# ospi_v11.net
KiCad netlist of a schematic drawn in EAGLE
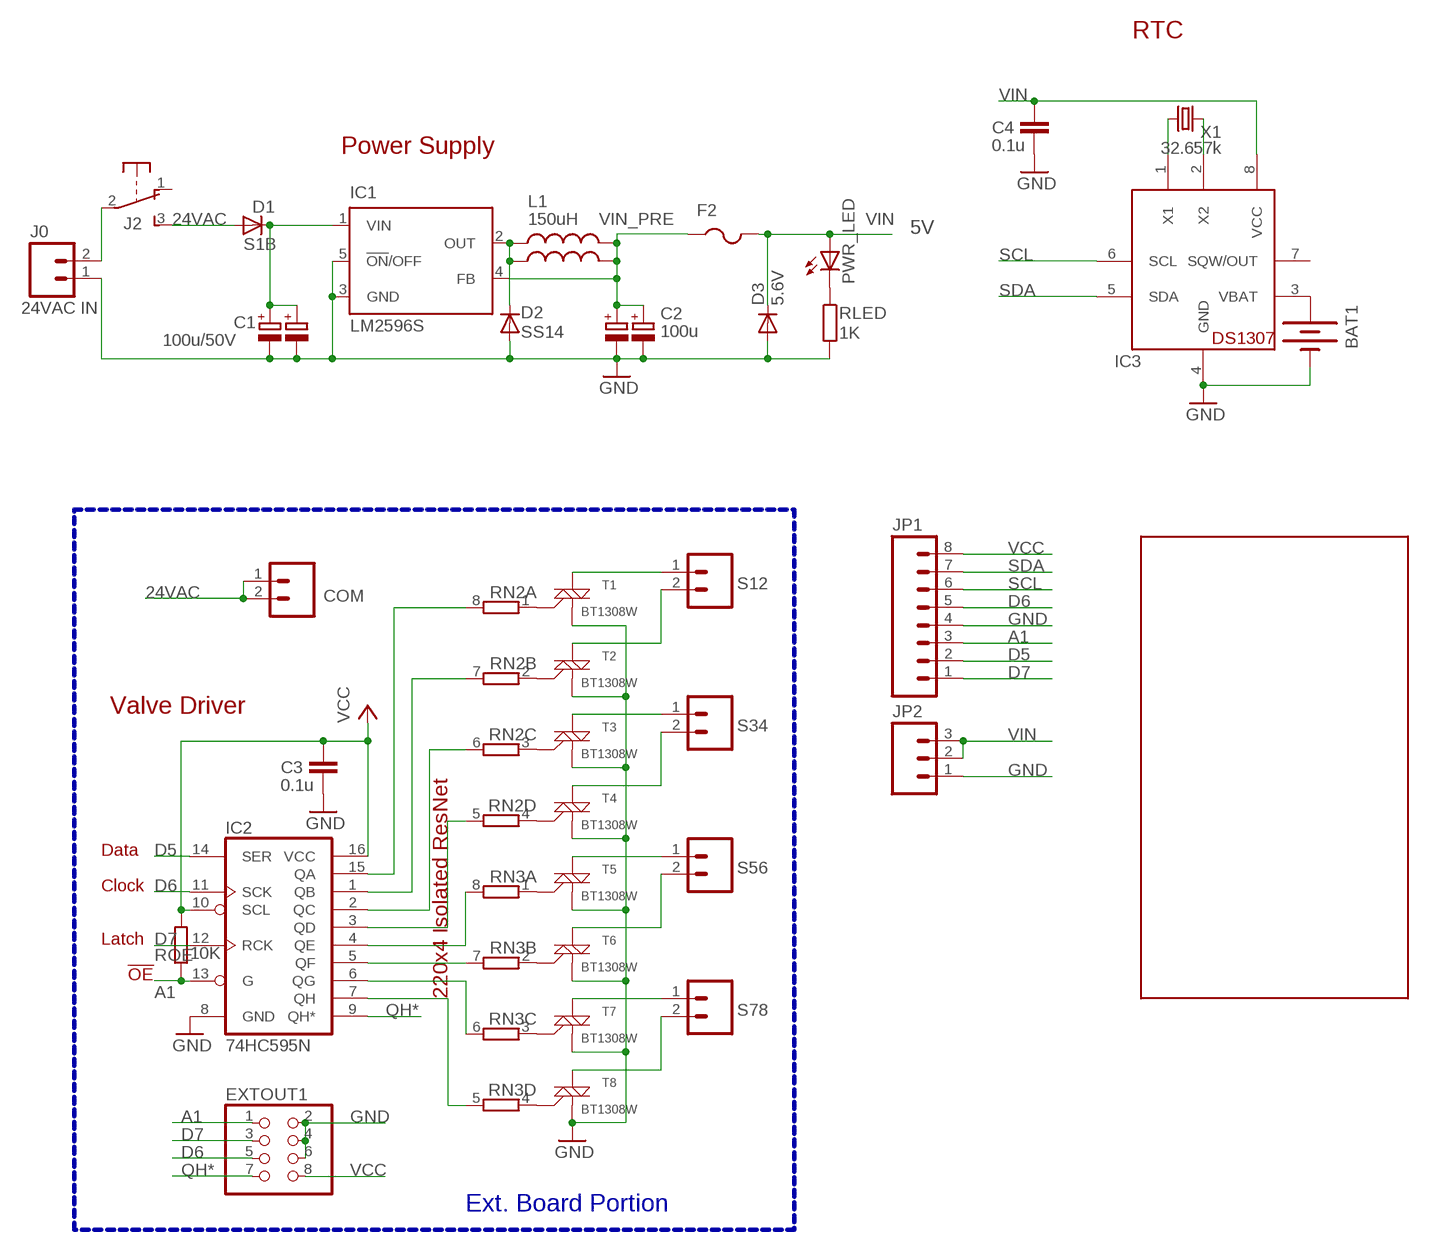
[diagram p0: schematic, sheet 1]

(export (version "E")
  (design (tool "Eeschema 10.0.6"))
  (components
    (comp (ref "BAT1")
      (value "BATTERYBATTERY_12MM_SMT")
      (footprint "eagle-import:BATTCON_12MM_SMT")
      (libsource (lib "eagle-import") (part "BATTERYBATTERY_12MM_SMT"))
    )
    (comp (ref "C1")
      (value "100u/50V")
      (footprint "eagle-import:E3,5-8")
      (libsource (lib "eagle-import") (part "CPOL-EUE3.5-8"))
    )
    (comp (ref "C1'")
      (value "100u")
      (footprint "eagle-import:PANASONIC_E")
      (libsource (lib "eagle-import") (part "CPOL-EUE"))
    )
    (comp (ref "C2")
      (value "100u")
      (footprint "eagle-import:E3,5-8")
      (libsource (lib "eagle-import") (part "CPOL-EUE3.5-8"))
    )
    (comp (ref "C2'")
      (value "100u")
      (footprint "eagle-import:PANASONIC_E")
      (libsource (lib "eagle-import") (part "CPOL-EUE"))
    )
    (comp (ref "C3")
      (value "0.1u")
      (footprint "eagle-import:C0805")
      (libsource (lib "eagle-import") (part "C-EUC0805"))
    )
    (comp (ref "C4")
      (value "0.1u")
      (footprint "eagle-import:C0805")
      (libsource (lib "eagle-import") (part "C-EUC0805"))
    )
    (comp (ref "COM")
      (value "M025MM")
      (footprint "eagle-import:SCREWTERMINAL-5MM-2")
      (libsource (lib "eagle-import") (part "M025MM"))
    )
    (comp (ref "D1")
      (value "S1B")
      (footprint "eagle-import:DO-214AC")
      (libsource (lib "eagle-import") (part "DIODE-DO-214AC"))
    )
    (comp (ref "D2")
      (value "SS14")
      (footprint "eagle-import:DO-214AC")
      (libsource (lib "eagle-import") (part "DIODE-DO-214AC"))
    )
    (comp (ref "D3")
      (value "5.6V")
      (footprint "eagle-import:MINIMELF")
      (libsource (lib "eagle-import") (part "DIODE-MINIMELF"))
    )
    (comp (ref "EXTOUT1")
      (value "PINHD-2X4/90")
      (footprint "eagle-import:2X04_90")
      (libsource (lib "eagle-import") (part "PINHD-2X4/90"))
    )
    (comp (ref "F2")
      (value "PTCFUSE-1812")
      (footprint "eagle-import:1812")
      (libsource (lib "eagle-import") (part "PTCFUSE-1812"))
    )
    (comp (ref "IC1")
      (value "LM2596S")
      (footprint "eagle-import:TO263-5")
      (fields (field (name "MF") "NATIONAL SEMICONDUCTOR") (field (name "MPN") "LM2596S-ADJ/NOPB"))
      (libsource (lib "eagle-import") (part "LM2596S"))
    )
    (comp (ref "IC2")
      (value "74HC595N")
      (footprint "eagle-import:SO16")
      (libsource (lib "eagle-import") (part "74595DLS"))
    )
    (comp (ref "IC3")
      (value "DS1307")
      (footprint "eagle-import:SO08")
      (libsource (lib "eagle-import") (part "DS1307SOIC"))
    )
    (comp (ref "J0")
      (value "24VAC IN")
      (footprint "eagle-import:SCREWTERMINAL-5MM-2")
      (libsource (lib "eagle-import") (part "M025MM"))
    )
    (comp (ref "J2")
      (value "EG1206")
      (footprint "eagle-import:EG1206")
      (libsource (lib "eagle-import") (part "EG1206"))
    )
    (comp (ref "JP1")
      (value "M08LOCK")
      (footprint "eagle-import:1X08_LOCK")
      (libsource (lib "eagle-import") (part "M08LOCK"))
    )
    (comp (ref "JP2")
      (value "M03LOCK")
      (footprint "eagle-import:1X03_LOCK")
      (libsource (lib "eagle-import") (part "M03LOCK"))
    )
    (comp (ref "L1")
      (value "150uH")
      (footprint "eagle-import:CDRH125")
      (libsource (lib "eagle-import") (part "INDUCTORPWR"))
    )
    (comp (ref "L1'")
      (value "100uH")
      (footprint "eagle-import:6000-XXXX-RC")
      (libsource (lib "eagle-import") (part "L-US6000-XXX-RC"))
    )
    (comp (ref "PWR_LED")
      (value "LEDCHIPLED_0805")
      (footprint "eagle-import:CHIPLED_0805")
      (libsource (lib "eagle-import") (part "LEDCHIPLED_0805"))
    )
    (comp (ref "RLED")
      (value "1K")
      (footprint "eagle-import:R0805")
      (libsource (lib "eagle-import") (part "R-EU_R0805"))
    )
    (comp (ref "RN2")
      (value "4R-NEXB38V")
      (footprint "eagle-import:EXB38V")
      (libsource (lib "eagle-import") (part "4R-NEXB38V"))
    )
    (comp (ref "RN3")
      (value "4R-NEXB38V")
      (footprint "eagle-import:EXB38V")
      (libsource (lib "eagle-import") (part "4R-NEXB38V"))
    )
    (comp (ref "ROE")
      (value "10K")
      (footprint "eagle-import:R0805")
      (libsource (lib "eagle-import") (part "R-EU_R0805"))
    )
    (comp (ref "S12")
      (value "M025MM")
      (footprint "eagle-import:SCREWTERMINAL-5MM-2")
      (libsource (lib "eagle-import") (part "M025MM"))
    )
    (comp (ref "S34")
      (value "M025MM")
      (footprint "eagle-import:SCREWTERMINAL-5MM-2")
      (libsource (lib "eagle-import") (part "M025MM"))
    )
    (comp (ref "S56")
      (value "M025MM")
      (footprint "eagle-import:SCREWTERMINAL-5MM-2")
      (libsource (lib "eagle-import") (part "M025MM"))
    )
    (comp (ref "S78")
      (value "M025MM")
      (footprint "eagle-import:SCREWTERMINAL-5MM-2")
      (libsource (lib "eagle-import") (part "M025MM"))
    )
    (comp (ref "T1")
      (value "BT1308W")
      (footprint "eagle-import:SOT223")
      (libsource (lib "eagle-import") (part "MAC97SOT223"))
    )
    (comp (ref "T2")
      (value "BT1308W")
      (footprint "eagle-import:SOT223")
      (libsource (lib "eagle-import") (part "MAC97SOT223"))
    )
    (comp (ref "T3")
      (value "BT1308W")
      (footprint "eagle-import:SOT223")
      (libsource (lib "eagle-import") (part "MAC97SOT223"))
    )
    (comp (ref "T4")
      (value "BT1308W")
      (footprint "eagle-import:SOT223")
      (libsource (lib "eagle-import") (part "MAC97SOT223"))
    )
    (comp (ref "T5")
      (value "BT1308W")
      (footprint "eagle-import:SOT223")
      (libsource (lib "eagle-import") (part "MAC97SOT223"))
    )
    (comp (ref "T6")
      (value "BT1308W")
      (footprint "eagle-import:SOT223")
      (libsource (lib "eagle-import") (part "MAC97SOT223"))
    )
    (comp (ref "T7")
      (value "BT1308W")
      (footprint "eagle-import:SOT223")
      (libsource (lib "eagle-import") (part "MAC97SOT223"))
    )
    (comp (ref "T8")
      (value "BT1308W")
      (footprint "eagle-import:SOT223")
      (libsource (lib "eagle-import") (part "MAC97SOT223"))
    )
    (comp (ref "U$2")
      (value "OSPI")
      (footprint "eagle-import:OSPI")
      (libsource (lib "eagle-import") (part "OSPI"))
    )
    (comp (ref "X1")
      (value "32.657k")
      (footprint "eagle-import:MM20SS")
      (libsource (lib "eagle-import") (part "CRYSTALMM20SS"))
    )
  )
  (nets
    (net (code "1") (name "/24VAC") (class "Default")
      (node (ref "COM") (pin "1") (pinfunction "1_1") (pintype "passive"))
      (node (ref "COM") (pin "2") (pinfunction "2_2") (pintype "passive"))
      (node (ref "D1") (pin "A") (pinfunction "A_A") (pintype "passive"))
      (node (ref "J2") (pin "3") (pinfunction "S_3") (pintype "passive"))
    )
    (net (code "2") (name "/A1") (class "Default")
      (node (ref "EXTOUT1") (pin "1") (pinfunction "1_1") (pintype "passive"))
      (node (ref "IC2") (pin "13") (pinfunction "G_13") (pintype "input"))
      (node (ref "JP1") (pin "3") (pinfunction "3_3") (pintype "passive"))
      (node (ref "ROE") (pin "1") (pinfunction "1_1") (pintype "passive"))
    )
    (net (code "3") (name "/D5") (class "Default")
      (node (ref "IC2") (pin "14") (pinfunction "SER_14") (pintype "input"))
      (node (ref "JP1") (pin "2") (pinfunction "2_2") (pintype "passive"))
    )
    (net (code "4") (name "/D6") (class "Default")
      (node (ref "EXTOUT1") (pin "5") (pinfunction "5_5") (pintype "passive"))
      (node (ref "IC2") (pin "11") (pinfunction "SCK_11") (pintype "input"))
      (node (ref "JP1") (pin "5") (pinfunction "5_5") (pintype "passive"))
    )
    (net (code "5") (name "/D7") (class "Default")
      (node (ref "EXTOUT1") (pin "3") (pinfunction "3_3") (pintype "passive"))
      (node (ref "IC2") (pin "12") (pinfunction "RCK_12") (pintype "input"))
      (node (ref "JP1") (pin "1") (pinfunction "1_1") (pintype "passive"))
    )
    (net (code "6") (name "/QH*") (class "Default")
      (node (ref "EXTOUT1") (pin "7") (pinfunction "7_7") (pintype "passive"))
      (node (ref "IC2") (pin "9") (pinfunction "QH*_9") (pintype "tri_state"))
    )
    (net (code "7") (name "/SCL") (class "Default")
      (node (ref "IC3") (pin "6") (pinfunction "SCL_6") (pintype "bidirectional"))
      (node (ref "JP1") (pin "6") (pinfunction "6_6") (pintype "passive"))
    )
    (net (code "8") (name "/SDA") (class "Default")
      (node (ref "IC3") (pin "5") (pinfunction "SDA_5") (pintype "bidirectional"))
      (node (ref "JP1") (pin "7") (pinfunction "7_7") (pintype "passive"))
    )
    (net (code "9") (name "/VIN") (class "Default")
      (node (ref "C4") (pin "1") (pinfunction "1_1") (pintype "passive"))
      (node (ref "D3") (pin "C") (pinfunction "C_C") (pintype "passive"))
      (node (ref "F2") (pin "2") (pinfunction "2_2") (pintype "passive"))
      (node (ref "IC3") (pin "8") (pinfunction "VCC_8") (pintype "power_in"))
      (node (ref "JP2") (pin "2") (pinfunction "2_2") (pintype "passive"))
      (node (ref "JP2") (pin "3") (pinfunction "3_3") (pintype "passive"))
      (node (ref "PWR_LED") (pin "A") (pinfunction "A_A") (pintype "passive"))
    )
    (net (code "10") (name "/VIN_PRE") (class "Default")
      (node (ref "C2") (pin "+") (pinfunction "+_+") (pintype "passive"))
      (node (ref "C2'") (pin "+") (pinfunction "+_+") (pintype "passive"))
      (node (ref "F2") (pin "1") (pinfunction "1_1") (pintype "passive"))
      (node (ref "IC1") (pin "4") (pinfunction "FB_4") (pintype "input"))
      (node (ref "L1") (pin "2") (pinfunction "2_2") (pintype "passive"))
      (node (ref "L1'") (pin "2") (pinfunction "2_2") (pintype "passive"))
    )
    (net (code "11") (name "GND") (class "Default")
      (node (ref "BAT1") (pin "P$1") (pinfunction "-_P$1") (pintype "power_in"))
      (node (ref "C1") (pin "-") (pinfunction "-_-") (pintype "passive"))
      (node (ref "C1'") (pin "-") (pinfunction "-_-") (pintype "passive"))
      (node (ref "C2") (pin "-") (pinfunction "-_-") (pintype "passive"))
      (node (ref "C2'") (pin "-") (pinfunction "-_-") (pintype "passive"))
      (node (ref "C3") (pin "2") (pinfunction "2_2") (pintype "passive"))
      (node (ref "C4") (pin "2") (pinfunction "2_2") (pintype "passive"))
      (node (ref "D2") (pin "A") (pinfunction "A_A") (pintype "passive"))
      (node (ref "D3") (pin "A") (pinfunction "A_A") (pintype "passive"))
      (node (ref "EXTOUT1") (pin "2") (pinfunction "2_2") (pintype "passive"))
      (node (ref "EXTOUT1") (pin "4") (pinfunction "4_4") (pintype "passive"))
      (node (ref "EXTOUT1") (pin "6") (pinfunction "6_6") (pintype "passive"))
      (node (ref "IC1") (pin "3") (pinfunction "GND_3") (pintype "power_in"))
      (node (ref "IC1") (pin "5") (pinfunction "~{ON}/OFF_5") (pintype "input"))
      (node (ref "IC2") (pin "8") (pinfunction "GND_8") (pintype "power_in"))
      (node (ref "IC3") (pin "4") (pinfunction "GND_4") (pintype "power_in"))
      (node (ref "J0") (pin "1") (pinfunction "1_1") (pintype "passive"))
      (node (ref "JP1") (pin "4") (pinfunction "4_4") (pintype "passive"))
      (node (ref "JP2") (pin "1") (pinfunction "1_1") (pintype "passive"))
      (node (ref "RLED") (pin "2") (pinfunction "2_2") (pintype "passive"))
      (node (ref "T1") (pin "1") (pinfunction "M1_1") (pintype "bidirectional"))
      (node (ref "T2") (pin "1") (pinfunction "M1_1") (pintype "bidirectional"))
      (node (ref "T3") (pin "1") (pinfunction "M1_1") (pintype "bidirectional"))
      (node (ref "T4") (pin "1") (pinfunction "M1_1") (pintype "bidirectional"))
      (node (ref "T5") (pin "1") (pinfunction "M1_1") (pintype "bidirectional"))
      (node (ref "T6") (pin "1") (pinfunction "M1_1") (pintype "bidirectional"))
      (node (ref "T7") (pin "1") (pinfunction "M1_1") (pintype "bidirectional"))
      (node (ref "T8") (pin "1") (pinfunction "M1_1") (pintype "bidirectional"))
    )
    (net (code "12") (name "Net-(BAT1-+)") (class "Default")
      (node (ref "BAT1") (pin "P$2") (pinfunction "+_P$2") (pintype "power_in"))
      (node (ref "IC3") (pin "3") (pinfunction "VBAT_3") (pintype "power_in"))
    )
    (net (code "13") (name "Net-(IC1-OUT)") (class "Default")
      (node (ref "D2") (pin "C") (pinfunction "C_C") (pintype "passive"))
      (node (ref "IC1") (pin "2") (pinfunction "OUT_2") (pintype "output"))
      (node (ref "L1") (pin "1") (pinfunction "1_1") (pintype "passive"))
      (node (ref "L1'") (pin "1") (pinfunction "1_1") (pintype "passive"))
    )
    (net (code "14") (name "Net-(IC1-VIN)") (class "Default")
      (node (ref "C1") (pin "+") (pinfunction "+_+") (pintype "passive"))
      (node (ref "C1'") (pin "+") (pinfunction "+_+") (pintype "passive"))
      (node (ref "D1") (pin "C") (pinfunction "C_C") (pintype "passive"))
      (node (ref "IC1") (pin "1") (pinfunction "VIN_1") (pintype "input"))
    )
    (net (code "15") (name "Net-(IC2-QA)") (class "Default")
      (node (ref "IC2") (pin "15") (pinfunction "QA_15") (pintype "tri_state"))
      (node (ref "RN2") (pin "8") (pinfunction "2_8") (pintype "passive"))
    )
    (net (code "16") (name "Net-(IC2-QB)") (class "Default")
      (node (ref "IC2") (pin "1") (pinfunction "QB_1") (pintype "tri_state"))
      (node (ref "RN2") (pin "7") (pinfunction "2_7") (pintype "passive"))
    )
    (net (code "17") (name "Net-(IC2-QC)") (class "Default")
      (node (ref "IC2") (pin "2") (pinfunction "QC_2") (pintype "tri_state"))
      (node (ref "RN2") (pin "6") (pinfunction "2_6") (pintype "passive"))
    )
    (net (code "18") (name "Net-(IC2-QD)") (class "Default")
      (node (ref "IC2") (pin "3") (pinfunction "QD_3") (pintype "tri_state"))
      (node (ref "RN2") (pin "5") (pinfunction "2_5") (pintype "passive"))
    )
    (net (code "19") (name "Net-(IC2-QE)") (class "Default")
      (node (ref "IC2") (pin "4") (pinfunction "QE_4") (pintype "tri_state"))
      (node (ref "RN3") (pin "8") (pinfunction "2_8") (pintype "passive"))
    )
    (net (code "20") (name "Net-(IC2-QF)") (class "Default")
      (node (ref "IC2") (pin "5") (pinfunction "QF_5") (pintype "tri_state"))
      (node (ref "RN3") (pin "7") (pinfunction "2_7") (pintype "passive"))
    )
    (net (code "21") (name "Net-(IC2-QG)") (class "Default")
      (node (ref "IC2") (pin "6") (pinfunction "QG_6") (pintype "tri_state"))
      (node (ref "RN3") (pin "6") (pinfunction "2_6") (pintype "passive"))
    )
    (net (code "22") (name "Net-(IC2-QH)") (class "Default")
      (node (ref "IC2") (pin "7") (pinfunction "QH_7") (pintype "tri_state"))
      (node (ref "RN3") (pin "5") (pinfunction "2_5") (pintype "passive"))
    )
    (net (code "23") (name "Net-(IC3-X1)") (class "Default")
      (node (ref "IC3") (pin "1") (pinfunction "X1_1") (pintype "passive"))
      (node (ref "X1") (pin "1") (pinfunction "1_1") (pintype "passive"))
    )
    (net (code "24") (name "Net-(IC3-X2)") (class "Default")
      (node (ref "IC3") (pin "2") (pinfunction "X2_2") (pintype "passive"))
      (node (ref "X1") (pin "4") (pinfunction "2_4") (pintype "passive"))
    )
    (net (code "25") (name "Net-(J2-P)") (class "Default")
      (node (ref "J0") (pin "2") (pinfunction "2_2") (pintype "passive"))
      (node (ref "J2") (pin "2") (pinfunction "P_2") (pintype "passive"))
    )
    (net (code "26") (name "Net-(PWR_LED-PadC)") (class "Default")
      (node (ref "PWR_LED") (pin "C") (pinfunction "C_C") (pintype "passive"))
      (node (ref "RLED") (pin "1") (pinfunction "1_1") (pintype "passive"))
    )
    (net (code "27") (name "Net-(RN2B-1)") (class "Default")
      (node (ref "RN2") (pin "2") (pinfunction "1_2") (pintype "passive"))
      (node (ref "T2") (pin "3") (pinfunction "G_3") (pintype "bidirectional"))
    )
    (net (code "28") (name "Net-(RN2C-1)") (class "Default")
      (node (ref "RN2") (pin "3") (pinfunction "1_3") (pintype "passive"))
      (node (ref "T3") (pin "3") (pinfunction "G_3") (pintype "bidirectional"))
    )
    (net (code "29") (name "Net-(RN2D-1)") (class "Default")
      (node (ref "RN2") (pin "4") (pinfunction "1_4") (pintype "passive"))
      (node (ref "T4") (pin "3") (pinfunction "G_3") (pintype "bidirectional"))
    )
    (net (code "30") (name "Net-(RN3B-1)") (class "Default")
      (node (ref "RN3") (pin "2") (pinfunction "1_2") (pintype "passive"))
      (node (ref "T6") (pin "3") (pinfunction "G_3") (pintype "bidirectional"))
    )
    (net (code "31") (name "Net-(RN3C-1)") (class "Default")
      (node (ref "RN3") (pin "3") (pinfunction "1_3") (pintype "passive"))
      (node (ref "T7") (pin "3") (pinfunction "G_3") (pintype "bidirectional"))
    )
    (net (code "32") (name "Net-(RN3D-1)") (class "Default")
      (node (ref "RN3") (pin "4") (pinfunction "1_4") (pintype "passive"))
      (node (ref "T8") (pin "3") (pinfunction "G_3") (pintype "bidirectional"))
    )
    (net (code "33") (name "Net-(T1-G)") (class "Default")
      (node (ref "RN2") (pin "1") (pinfunction "1_1") (pintype "passive"))
      (node (ref "T1") (pin "3") (pinfunction "G_3") (pintype "bidirectional"))
    )
    (net (code "34") (name "Net-(T1-M2)") (class "Default")
      (node (ref "S12") (pin "1") (pinfunction "1_1") (pintype "passive"))
      (node (ref "T1") (pin "4") (pinfunction "M2_4") (pintype "bidirectional"))
    )
    (net (code "35") (name "Net-(T2-M2)") (class "Default")
      (node (ref "S12") (pin "2") (pinfunction "2_2") (pintype "passive"))
      (node (ref "T2") (pin "4") (pinfunction "M2_4") (pintype "bidirectional"))
    )
    (net (code "36") (name "Net-(T3-M2)") (class "Default")
      (node (ref "S34") (pin "1") (pinfunction "1_1") (pintype "passive"))
      (node (ref "T3") (pin "4") (pinfunction "M2_4") (pintype "bidirectional"))
    )
    (net (code "37") (name "Net-(T4-M2)") (class "Default")
      (node (ref "S34") (pin "2") (pinfunction "2_2") (pintype "passive"))
      (node (ref "T4") (pin "4") (pinfunction "M2_4") (pintype "bidirectional"))
    )
    (net (code "38") (name "Net-(T5-G)") (class "Default")
      (node (ref "RN3") (pin "1") (pinfunction "1_1") (pintype "passive"))
      (node (ref "T5") (pin "3") (pinfunction "G_3") (pintype "bidirectional"))
    )
    (net (code "39") (name "Net-(T5-M2)") (class "Default")
      (node (ref "S56") (pin "1") (pinfunction "1_1") (pintype "passive"))
      (node (ref "T5") (pin "4") (pinfunction "M2_4") (pintype "bidirectional"))
    )
    (net (code "40") (name "Net-(T6-M2)") (class "Default")
      (node (ref "S56") (pin "2") (pinfunction "2_2") (pintype "passive"))
      (node (ref "T6") (pin "4") (pinfunction "M2_4") (pintype "bidirectional"))
    )
    (net (code "41") (name "Net-(T7-M2)") (class "Default")
      (node (ref "S78") (pin "1") (pinfunction "1_1") (pintype "passive"))
      (node (ref "T7") (pin "4") (pinfunction "M2_4") (pintype "bidirectional"))
    )
    (net (code "42") (name "Net-(T8-M2)") (class "Default")
      (node (ref "S78") (pin "2") (pinfunction "2_2") (pintype "passive"))
      (node (ref "T8") (pin "4") (pinfunction "M2_4") (pintype "bidirectional"))
    )
    (net (code "43") (name "VCC") (class "Default")
      (node (ref "C3") (pin "1") (pinfunction "1_1") (pintype "passive"))
      (node (ref "EXTOUT1") (pin "8") (pinfunction "8_8") (pintype "passive"))
      (node (ref "IC2") (pin "10") (pinfunction "SCL_10") (pintype "input"))
      (node (ref "IC2") (pin "16") (pinfunction "VCC_16") (pintype "power_in"))
      (node (ref "JP1") (pin "8") (pinfunction "8_8") (pintype "passive"))
      (node (ref "ROE") (pin "2") (pinfunction "2_2") (pintype "passive"))
    )
    (net (code "44") (name "unconnected-(IC3-SQW{slash}OUT-Pad7)") (class "Default")
      (node (ref "IC3") (pin "7") (pinfunction "SQW/OUT_7") (pintype "bidirectional"))
    )
    (net (code "45") (name "unconnected-(J2-O-Pad1)") (class "Default")
      (node (ref "J2") (pin "1") (pinfunction "O_1") (pintype "passive"))
    )
  )
)
